# USBINFRTransiever_Power.net
KiCad netlist of a schematic drawn in Altium Designer
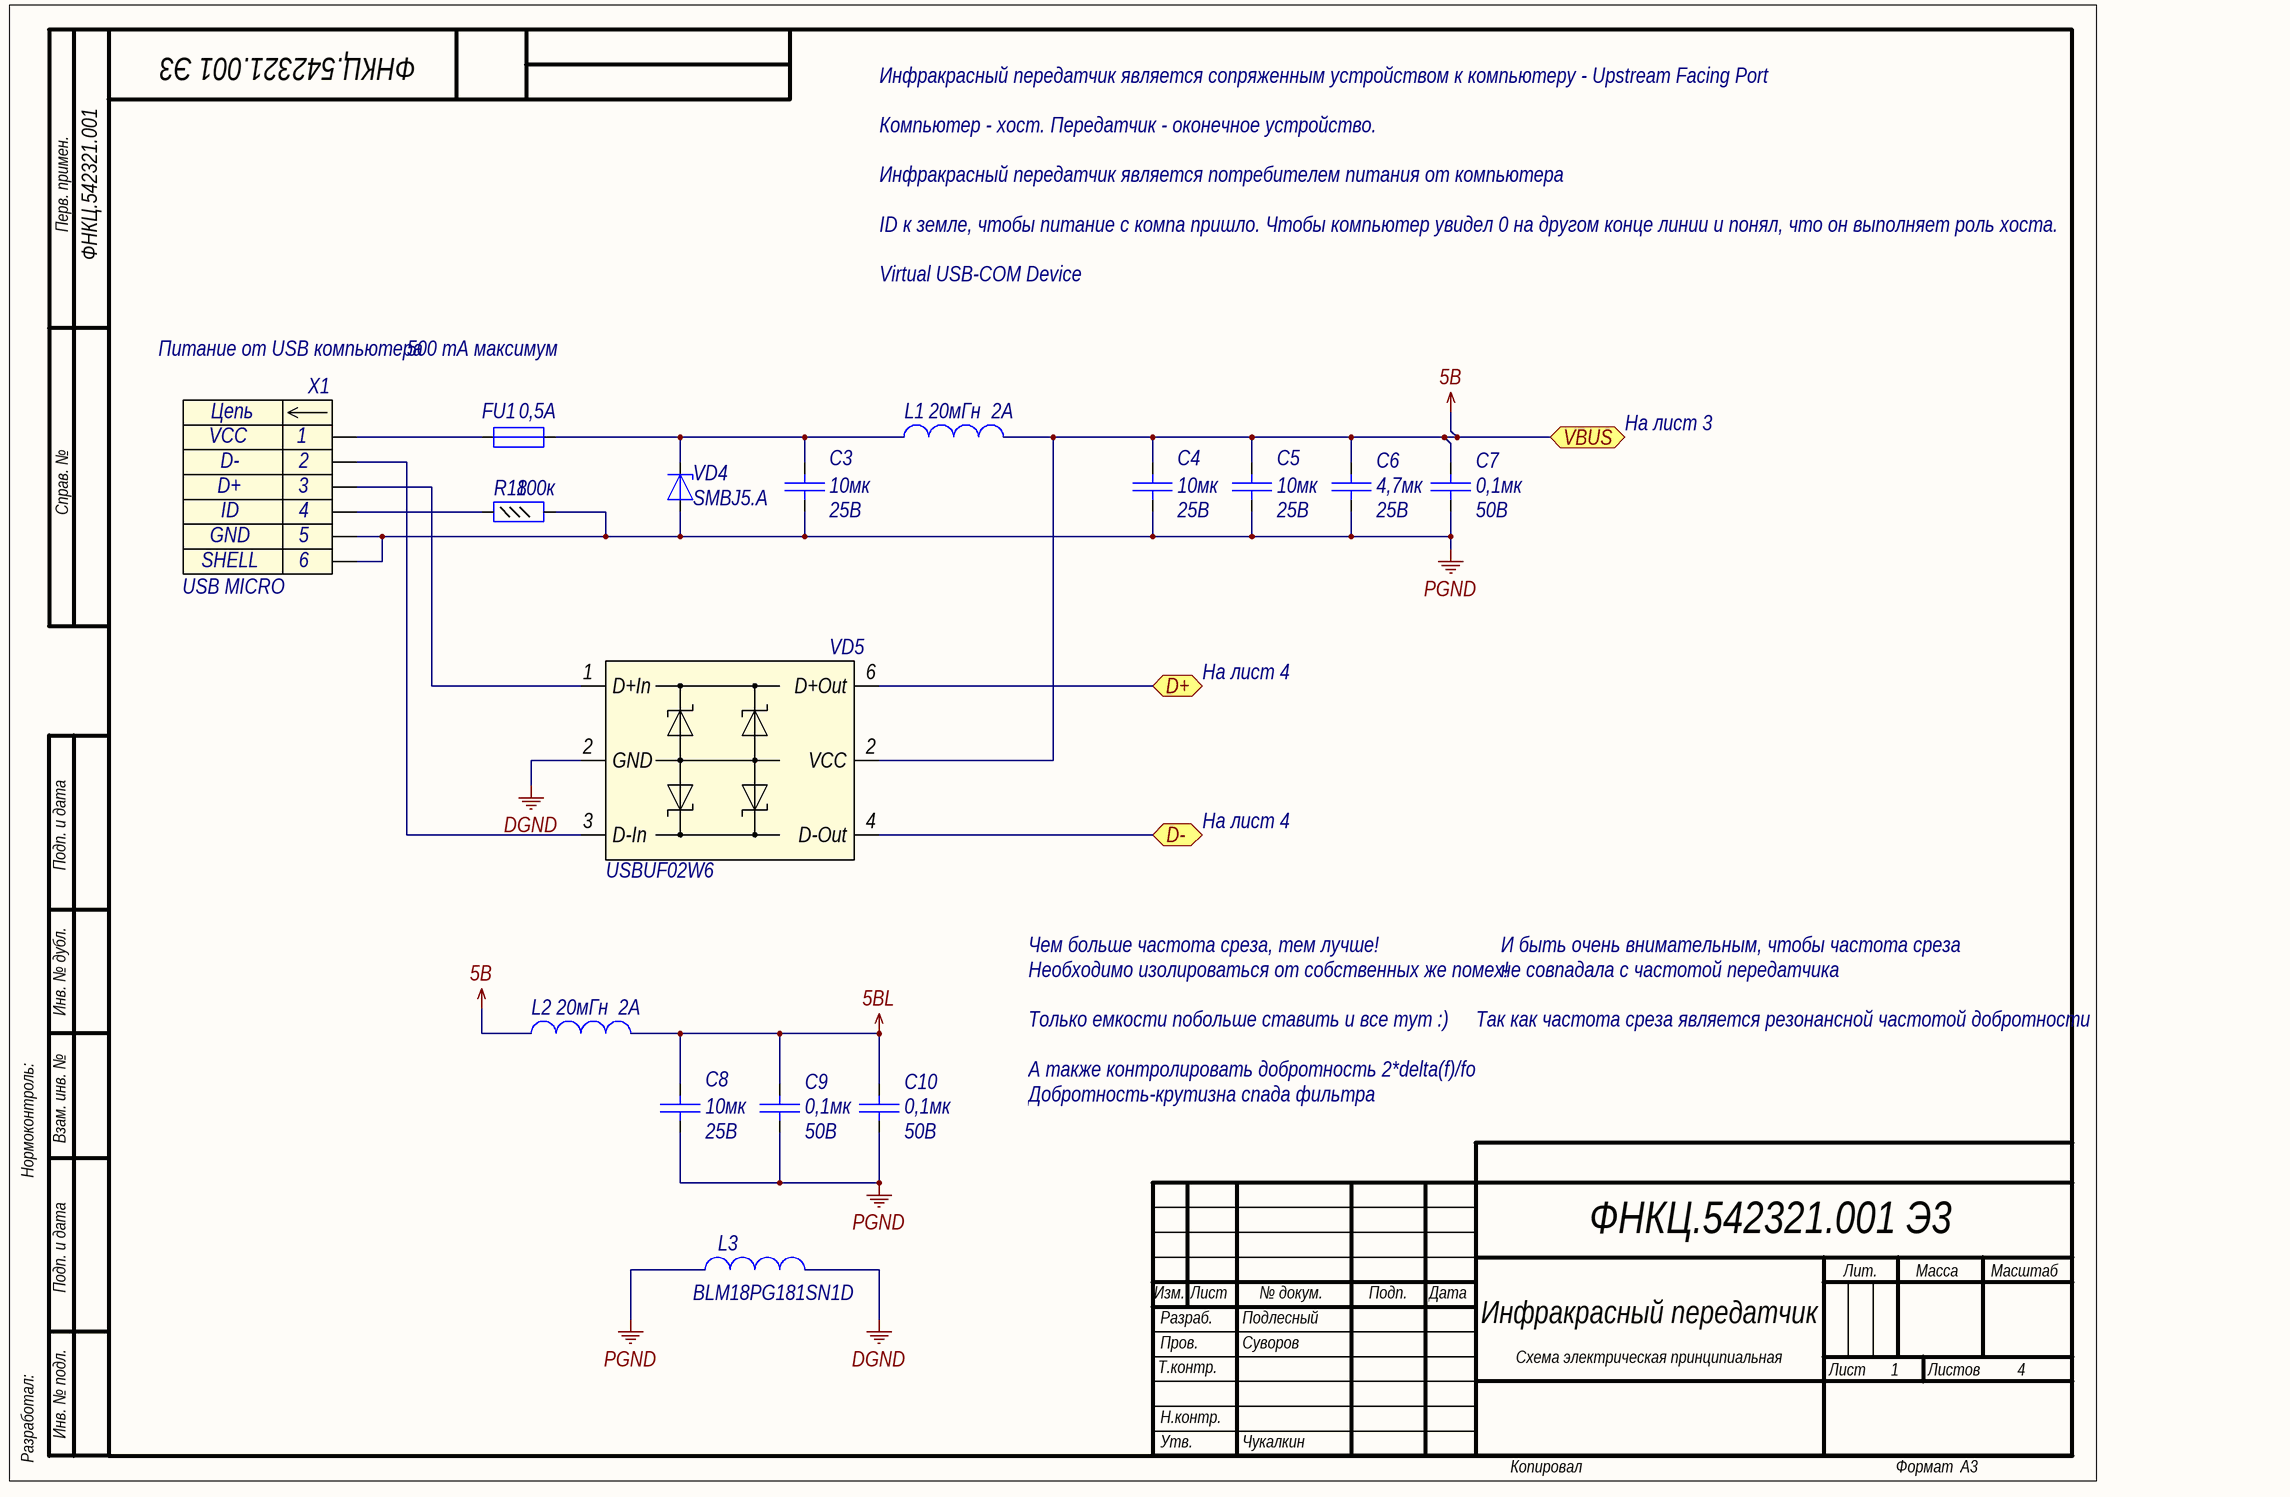
[diagram p0: USBINFRTransiever_Power.SchDoc]

(export (version "E")
  (design (tool "Eeschema 10.0.6"))
  (components
    (comp (ref "C3")
      (value "10мк")
      (footprint "C1206")
      (description "Конденсатор")
      (fields
        (field (name "VOLTAGE") "25В")
        (field (name "PART NUMBER") "GRM31CR71E106KA12L*")
        (field (name "Comment") "Capacitor")
      )
      (libsource (lib "MOP44") (part "Capacitor"))
    )
    (comp (ref "C4")
      (value "10мк")
      (footprint "C1206")
      (description "Конденсатор")
      (fields
        (field (name "VOLTAGE") "25В")
        (field (name "PART NUMBER") "GRM31CR71E106KA12L*")
        (field (name "Comment") "Capacitor")
      )
      (libsource (lib "MOP44") (part "Capacitor"))
    )
    (comp (ref "C5")
      (value "10мк")
      (footprint "C1206")
      (description "Конденсатор")
      (fields
        (field (name "VOLTAGE") "25В")
        (field (name "PART NUMBER") "GRM31CR71E106KA12L*")
        (field (name "Comment") "Capacitor")
      )
      (libsource (lib "MOP44") (part "Capacitor"))
    )
    (comp (ref "C6")
      (value "4,7мк")
      (footprint "C0805")
      (description "Конденсатор")
      (fields
        (field (name "VOLTAGE") "25B")
        (field (name "PART NUMBER") "GRM21BR61E475KA12L")
        (field (name "Comment") "Capacitor")
      )
      (libsource (lib "MOP44") (part "Capacitor"))
    )
    (comp (ref "C7")
      (value "0,1мк")
      (footprint "C0805")
      (description "Конденсатор")
      (fields
        (field (name "VOLTAGE") "50B")
        (field (name "PART NUMBER") "GRM21BR71H104K**")
        (field (name "Comment") "Capacitor")
      )
      (libsource (lib "MOP44") (part "Capacitor"))
    )
    (comp (ref "C8")
      (value "10мк")
      (footprint "C1206")
      (description "Конденсатор")
      (fields
        (field (name "VOLTAGE") "25В")
        (field (name "PART NUMBER") "GRM31CR71E106KA12L*")
        (field (name "Comment") "Capacitor")
      )
      (libsource (lib "MOP44") (part "Capacitor"))
    )
    (comp (ref "C9")
      (value "0,1мк")
      (footprint "C0805")
      (description "Конденсатор")
      (fields
        (field (name "VOLTAGE") "50B")
        (field (name "PART NUMBER") "GRM21BR71H104K**")
        (field (name "Comment") "Capacitor")
      )
      (libsource (lib "MOP44") (part "Capacitor"))
    )
    (comp (ref "C10")
      (value "0,1мк")
      (footprint "C0805")
      (description "Конденсатор")
      (fields
        (field (name "VOLTAGE") "50B")
        (field (name "PART NUMBER") "GRM21BR71H104K**")
        (field (name "Comment") "Capacitor")
      )
      (libsource (lib "MOP44") (part "Capacitor"))
    )
    (comp (ref "FU1")
      (value "Fuse")
      (footprint "FUSE812")
      (description "Предохранитель")
      (fields (field (name "I HOLD") "0,5A") (field (name "PART NUMBER") "MF-MSMF050"))
      (libsource (lib "MOP44") (part "Fuse"))
    )
    (comp (ref "L1")
      (value "20мГн")
      (footprint "L0805")
      (description "EMI Suppression Filter")
      (fields
        (field (name "RATED CURRENT") "2А")
        (field (name "PART NUMBER") "BLM21PG221SN1D")
        (field (name "Comment") "Inductor")
      )
      (libsource (lib "MOP44") (part "Inductor"))
    )
    (comp (ref "L2")
      (value "20мГн")
      (footprint "L0805")
      (description "EMI Suppression Filter")
      (fields
        (field (name "RATED CURRENT") "2А")
        (field (name "PART NUMBER") "BLM21PG221SN1D")
        (field (name "Comment") "Inductor")
      )
      (libsource (lib "MOP44") (part "Inductor"))
    )
    (comp (ref "L3")
      (value "Inductor")
      (footprint "L0603")
      (description "EMI Suppression Filter")
      (fields (field (name "PART NUMBER") "BLM18PG181SN1D"))
      (libsource (lib "MOP44") (part "Inductor"))
    )
    (comp (ref "R18")
      (value "100к")
      (footprint "R0603")
      (description "Резистор")
      (fields (field (name "PART NUMBER") "RC0603FR-07100KL") (field (name "POWER") "0,062Вт"))
      (libsource (lib "MOP44") (part "Resistor_0,062Вт"))
    )
    (comp (ref "VD4")
      (value "DiodeZener")
      (footprint "SMB")
      (description "Cтабилитрон (лавинный выпрямительный диод) односторонний")
      (fields (field (name "PART NUMBER") "SMBJ5.A"))
      (libsource (lib "MOP44") (part "DiodeZener"))
    )
    (comp (ref "VD5")
      (value "USBUF")
      (footprint "SOT323-6L")
      (description "EMEMI filter and line termination for USB upstream ports")
      (fields (field (name "PART NUMBER") "USBUF02W6"))
      (libsource (lib "MOP44") (part "USBUF"))
    )
    (comp (ref "X1")
      (value "USB MICRO")
      (footprint "USB-B Micro")
      (fields (field (name "PART NUMBER") "KLS1-233-0-0-1-T"))
      (libsource (lib "MOP44") (part "USB MICRO"))
    )
  )
  (nets
    (net (code "1") (name "/D+") (class "Default")
      (node (ref "VD5") (pin "6") (pinfunction "D+Out_6") (pintype "passive"))
    )
    (net (code "2") (name "/D-") (class "Default")
      (node (ref "VD5") (pin "4") (pinfunction "D-Out_4") (pintype "passive"))
    )
    (net (code "3") (name "5В") (class "Default")
      (node (ref "C4") (pin "2") (pinfunction "2_2") (pintype "passive"))
      (node (ref "C5") (pin "2") (pinfunction "2_2") (pintype "passive"))
      (node (ref "C6") (pin "2") (pinfunction "2_2") (pintype "passive"))
      (node (ref "C7") (pin "2") (pinfunction "2_2") (pintype "passive"))
      (node (ref "L1") (pin "2") (pinfunction "2_2") (pintype "passive"))
      (node (ref "L2") (pin "1") (pinfunction "1_1") (pintype "passive"))
      (node (ref "VD5") (pin "2") (pinfunction "VCC_2") (pintype "passive"))
    )
    (net (code "4") (name "5ВL") (class "Default")
      (node (ref "C10") (pin "2") (pinfunction "2_2") (pintype "passive"))
      (node (ref "C8") (pin "2") (pinfunction "2_2") (pintype "passive"))
      (node (ref "C9") (pin "2") (pinfunction "2_2") (pintype "passive"))
      (node (ref "L2") (pin "2") (pinfunction "2_2") (pintype "passive"))
    )
    (net (code "5") (name "DGND") (class "Default")
      (node (ref "L3") (pin "2") (pinfunction "2_2") (pintype "passive"))
      (node (ref "VD5") (pin "2") (pinfunction "GND_2") (pintype "passive"))
    )
    (net (code "6") (name "Net-(FU1-Pad1)") (class "Default")
      (node (ref "FU1") (pin "1") (pinfunction "1_1") (pintype "passive"))
      (node (ref "X1") (pin "1") (pinfunction "1_1") (pintype "passive"))
    )
    (net (code "7") (name "Net-(R18-Pad1)") (class "Default")
      (node (ref "R18") (pin "1") (pinfunction "1_1") (pintype "passive"))
      (node (ref "X1") (pin "4") (pinfunction "4_4") (pintype "passive"))
    )
    (net (code "8") (name "Net-(VD4-K)") (class "Default")
      (node (ref "C3") (pin "2") (pinfunction "2_2") (pintype "passive"))
      (node (ref "FU1") (pin "2") (pinfunction "2_2") (pintype "passive"))
      (node (ref "L1") (pin "1") (pinfunction "1_1") (pintype "passive"))
      (node (ref "VD4") (pin "1") (pinfunction "K_1") (pintype "passive"))
    )
    (net (code "9") (name "Net-(VD5-D+In)") (class "Default")
      (node (ref "VD5") (pin "1") (pinfunction "D+In_1") (pintype "passive"))
      (node (ref "X1") (pin "3") (pinfunction "3_3") (pintype "passive"))
    )
    (net (code "10") (name "Net-(VD5-D-In)") (class "Default")
      (node (ref "VD5") (pin "3") (pinfunction "D-In_3") (pintype "passive"))
      (node (ref "X1") (pin "2") (pinfunction "2_2") (pintype "passive"))
    )
    (net (code "11") (name "PGND") (class "Default")
      (node (ref "C10") (pin "1") (pinfunction "1_1") (pintype "passive"))
      (node (ref "C3") (pin "1") (pinfunction "1_1") (pintype "passive"))
      (node (ref "C4") (pin "1") (pinfunction "1_1") (pintype "passive"))
      (node (ref "C5") (pin "1") (pinfunction "1_1") (pintype "passive"))
      (node (ref "C6") (pin "1") (pinfunction "1_1") (pintype "passive"))
      (node (ref "C7") (pin "1") (pinfunction "1_1") (pintype "passive"))
      (node (ref "C8") (pin "1") (pinfunction "1_1") (pintype "passive"))
      (node (ref "C9") (pin "1") (pinfunction "1_1") (pintype "passive"))
      (node (ref "L3") (pin "1") (pinfunction "1_1") (pintype "passive"))
      (node (ref "R18") (pin "2") (pinfunction "2_2") (pintype "passive"))
      (node (ref "VD4") (pin "2") (pinfunction "A_2") (pintype "passive"))
      (node (ref "X1") (pin "5") (pinfunction "5_5") (pintype "passive"))
      (node (ref "X1") (pin "6") (pinfunction "6_6") (pintype "passive"))
    )
  )
)
